# Explore_Labs_3D_Gyroscope_L3GD20H_Breako.net
KiCad netlist of a schematic drawn in EAGLE
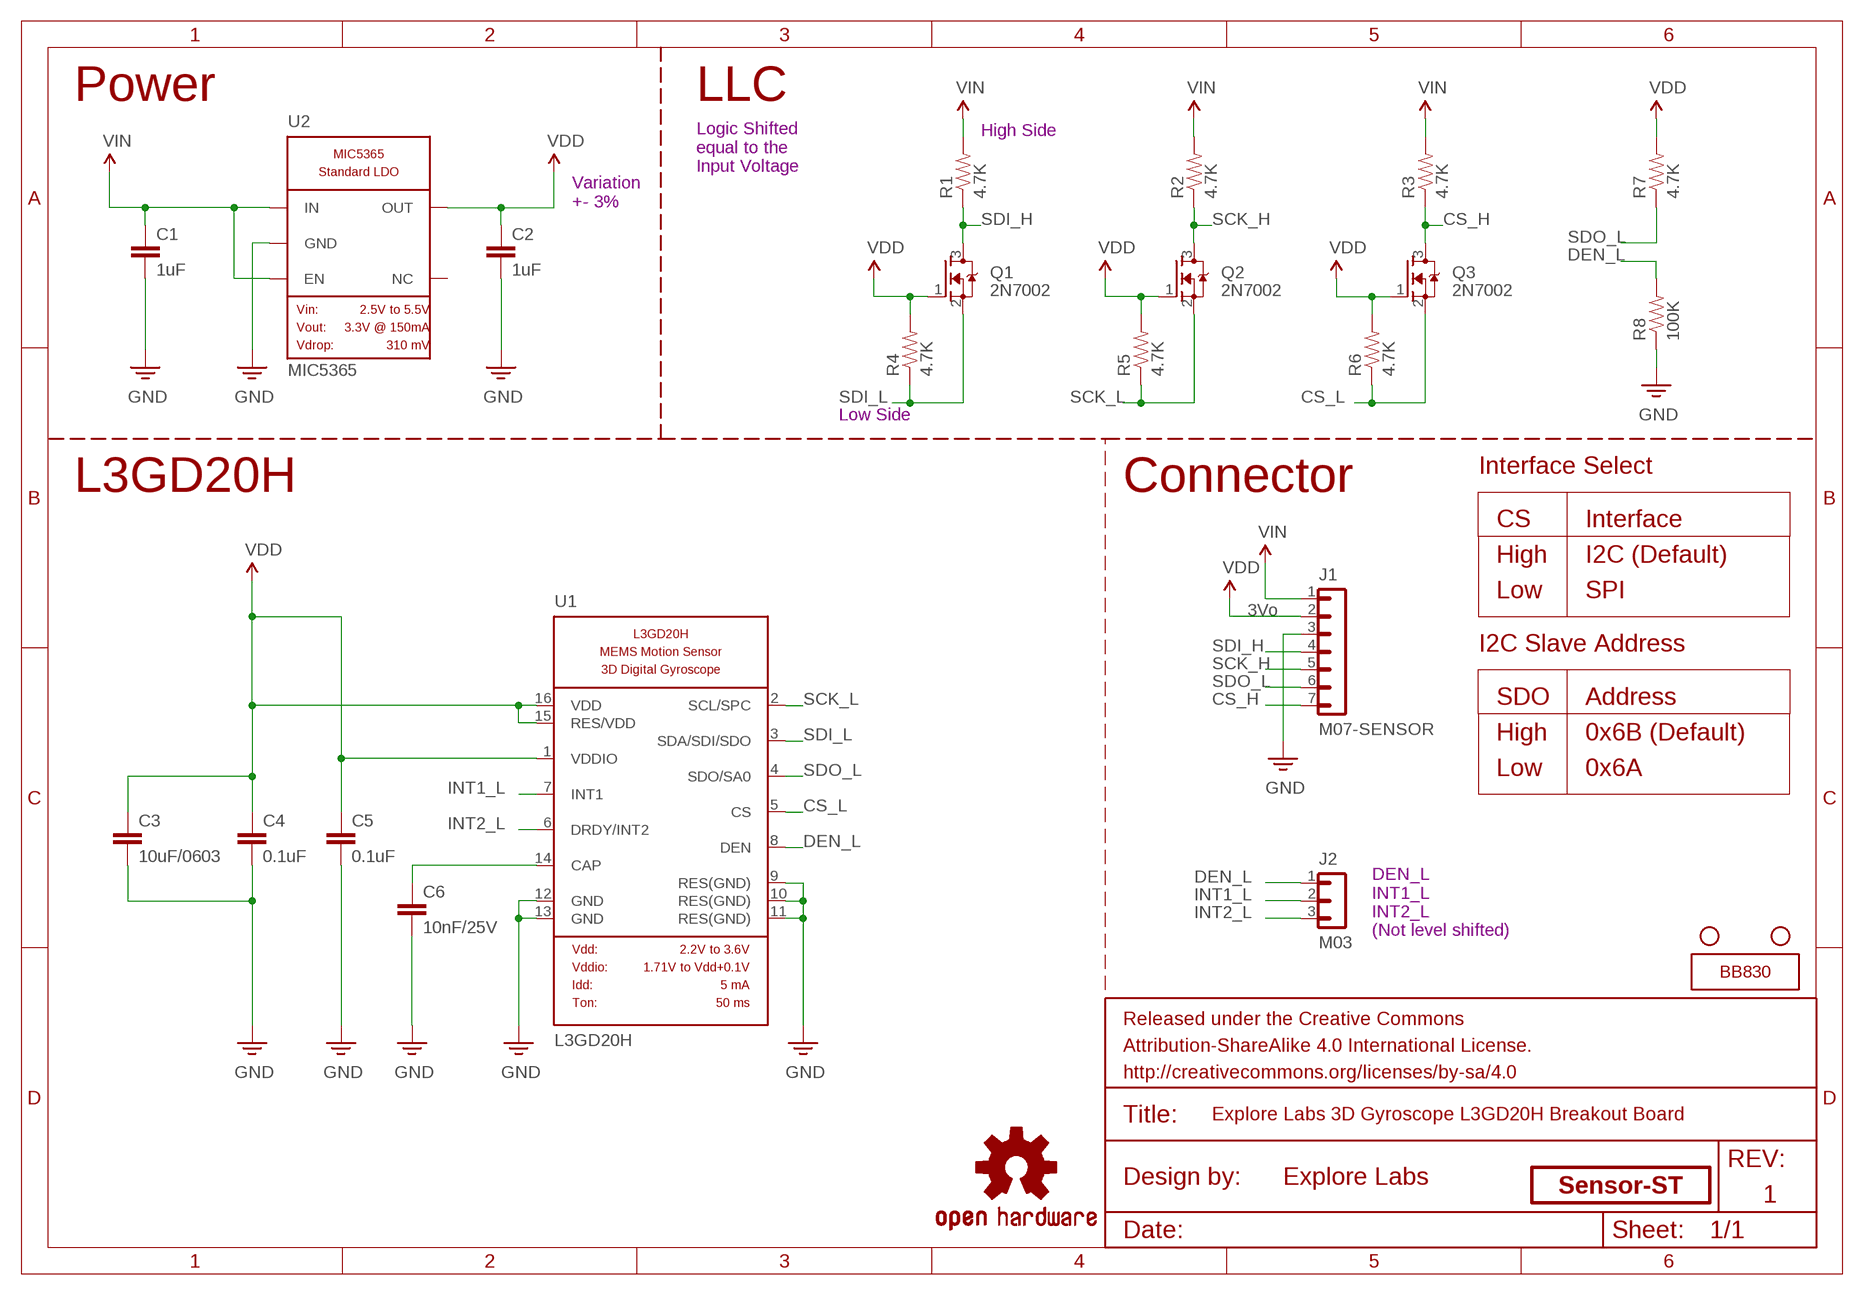
[diagram p0: schematic, sheet 1]

(export (version "E")
  (design (tool "Eeschema 10.0.6"))
  (components
    (comp (ref "C1")
      (value "1uF")
      (footprint "eagle-import:0402-CAP")
      (libsource (lib "eagle-import") (part "CAPACITOR-0402"))
    )
    (comp (ref "C2")
      (value "1uF")
      (footprint "eagle-import:0402-CAP")
      (libsource (lib "eagle-import") (part "CAPACITOR-0402"))
    )
    (comp (ref "C3")
      (value "10uF/0603")
      (footprint "eagle-import:0603-CAP")
      (libsource (lib "eagle-import") (part "CAPACITOR-0603"))
    )
    (comp (ref "C4")
      (value "0.1uF")
      (footprint "eagle-import:0402-CAP")
      (libsource (lib "eagle-import") (part "CAPACITOR-0402"))
    )
    (comp (ref "C5")
      (value "0.1uF")
      (footprint "eagle-import:0402-CAP")
      (libsource (lib "eagle-import") (part "CAPACITOR-0402"))
    )
    (comp (ref "C6")
      (value "10nF/25V")
      (footprint "eagle-import:0402-CAP")
      (libsource (lib "eagle-import") (part "CAPACITOR-0402"))
    )
    (comp (ref "H1")
      (value "STAND-OFF")
      (footprint "eagle-import:STAND-OFF")
      (libsource (lib "eagle-import") (part "STAND-OFF"))
    )
    (comp (ref "H2")
      (value "STAND-OFF")
      (footprint "eagle-import:STAND-OFF")
      (libsource (lib "eagle-import") (part "STAND-OFF"))
    )
    (comp (ref "J1")
      (value "M07-SENSOR")
      (footprint "eagle-import:1X07-SENSOR-SPI")
      (libsource (lib "eagle-import") (part "M07-SENSOR"))
    )
    (comp (ref "J2")
      (value "M03")
      (footprint "eagle-import:1X03")
      (libsource (lib "eagle-import") (part "M03"))
    )
    (comp (ref "Q1")
      (value "2N7002")
      (footprint "eagle-import:SOT23")
      (libsource (lib "eagle-import") (part "MOSFET-N-2N7002P"))
    )
    (comp (ref "Q2")
      (value "2N7002")
      (footprint "eagle-import:SOT23")
      (libsource (lib "eagle-import") (part "MOSFET-N-2N7002P"))
    )
    (comp (ref "Q3")
      (value "2N7002")
      (footprint "eagle-import:SOT23")
      (libsource (lib "eagle-import") (part "MOSFET-N-2N7002P"))
    )
    (comp (ref "R1")
      (value "4.7K")
      (footprint "eagle-import:0402-RES")
      (libsource (lib "eagle-import") (part "RESISTOR-0402"))
    )
    (comp (ref "R2")
      (value "4.7K")
      (footprint "eagle-import:0402-RES")
      (libsource (lib "eagle-import") (part "RESISTOR-0402"))
    )
    (comp (ref "R3")
      (value "4.7K")
      (footprint "eagle-import:0402-RES")
      (libsource (lib "eagle-import") (part "RESISTOR-0402"))
    )
    (comp (ref "R4")
      (value "4.7K")
      (footprint "eagle-import:0402-RES")
      (libsource (lib "eagle-import") (part "RESISTOR-0402"))
    )
    (comp (ref "R5")
      (value "4.7K")
      (footprint "eagle-import:0402-RES")
      (libsource (lib "eagle-import") (part "RESISTOR-0402"))
    )
    (comp (ref "R6")
      (value "4.7K")
      (footprint "eagle-import:0402-RES")
      (libsource (lib "eagle-import") (part "RESISTOR-0402"))
    )
    (comp (ref "R7")
      (value "4.7K")
      (footprint "eagle-import:0402-RES")
      (libsource (lib "eagle-import") (part "RESISTOR-0402"))
    )
    (comp (ref "R8")
      (value "100K")
      (footprint "eagle-import:0402-RES")
      (libsource (lib "eagle-import") (part "RESISTOR-0402"))
    )
    (comp (ref "U1")
      (value "L3GD20H")
      (footprint "eagle-import:LGA16")
      (libsource (lib "eagle-import") (part "L3GD20H"))
    )
    (comp (ref "U2")
      (value "MIC5365")
      (footprint "eagle-import:SOT23-LDO")
      (libsource (lib "eagle-import") (part "MIC5365"))
    )
    (comp (ref "ZZ1")
      (value "EXPLORE-LABS-LOGO-2-0.25")
      (footprint "eagle-import:EXLABS_LOGO_0.25")
      (libsource (lib "eagle-import") (part "EXPLORE-LABS-LOGO-2-0.25"))
    )
    (comp (ref "ZZ2")
      (value "OSHW-LOGOBOTTOM")
      (footprint "eagle-import:OSHW-LOGO-M-BOTTOM")
      (libsource (lib "eagle-import") (part "OSHW-LOGOBOTTOM"))
    )
    (comp (ref "ZZ3")
      (value "SENSOR-ST")
      (footprint "eagle-import:SENSOR-ST")
      (libsource (lib "eagle-import") (part "SENSOR-ST"))
    )
    (comp (ref "ZZ4")
      (value "BREADBOARD-830")
      (footprint "eagle-import:BREADBOARD-830")
      (libsource (lib "eagle-import") (part "BREADBOARD-830"))
    )
  )
  (nets
    (net (code "1") (name "/CS_H") (class "Default")
      (node (ref "J1") (pin "7") (pinfunction "7_7") (pintype "passive"))
      (node (ref "Q3") (pin "3") (pinfunction "D_3") (pintype "bidirectional"))
      (node (ref "R3") (pin "1") (pinfunction "1_1") (pintype "passive"))
    )
    (net (code "2") (name "/CS_L") (class "Default")
      (node (ref "Q3") (pin "2") (pinfunction "S_2") (pintype "bidirectional"))
      (node (ref "R6") (pin "1") (pinfunction "1_1") (pintype "passive"))
      (node (ref "U1") (pin "5") (pinfunction "CS_5") (pintype "bidirectional"))
    )
    (net (code "3") (name "/DEN_L") (class "Default")
      (node (ref "J2") (pin "1") (pinfunction "1_1") (pintype "passive"))
      (node (ref "R8") (pin "2") (pinfunction "2_2") (pintype "passive"))
      (node (ref "U1") (pin "8") (pinfunction "DEN_8") (pintype "bidirectional"))
    )
    (net (code "4") (name "/INT1_L") (class "Default")
      (node (ref "J2") (pin "2") (pinfunction "2_2") (pintype "passive"))
      (node (ref "U1") (pin "7") (pinfunction "INT1_7") (pintype "bidirectional"))
    )
    (net (code "5") (name "/INT2_L") (class "Default")
      (node (ref "J2") (pin "3") (pinfunction "3_3") (pintype "passive"))
      (node (ref "U1") (pin "6") (pinfunction "DRDY/INT2_6") (pintype "bidirectional"))
    )
    (net (code "6") (name "/SCK_H") (class "Default")
      (node (ref "J1") (pin "5") (pinfunction "5_5") (pintype "passive"))
      (node (ref "Q2") (pin "3") (pinfunction "D_3") (pintype "bidirectional"))
      (node (ref "R2") (pin "1") (pinfunction "1_1") (pintype "passive"))
    )
    (net (code "7") (name "/SCK_L") (class "Default")
      (node (ref "Q2") (pin "2") (pinfunction "S_2") (pintype "bidirectional"))
      (node (ref "R5") (pin "1") (pinfunction "1_1") (pintype "passive"))
      (node (ref "U1") (pin "2") (pinfunction "SCL/SPC_2") (pintype "bidirectional"))
    )
    (net (code "8") (name "/SDI_H") (class "Default")
      (node (ref "J1") (pin "4") (pinfunction "4_4") (pintype "passive"))
      (node (ref "Q1") (pin "3") (pinfunction "D_3") (pintype "bidirectional"))
      (node (ref "R1") (pin "1") (pinfunction "1_1") (pintype "passive"))
    )
    (net (code "9") (name "/SDI_L") (class "Default")
      (node (ref "Q1") (pin "2") (pinfunction "S_2") (pintype "bidirectional"))
      (node (ref "R4") (pin "1") (pinfunction "1_1") (pintype "passive"))
      (node (ref "U1") (pin "3") (pinfunction "SDA/SDI/SDO_3") (pintype "bidirectional"))
    )
    (net (code "10") (name "/SDO_L") (class "Default")
      (node (ref "J1") (pin "6") (pinfunction "6_6") (pintype "passive"))
      (node (ref "R7") (pin "1") (pinfunction "1_1") (pintype "passive"))
      (node (ref "U1") (pin "4") (pinfunction "SDO/SA0_4") (pintype "bidirectional"))
    )
    (net (code "11") (name "GND") (class "Default")
      (node (ref "C1") (pin "2") (pinfunction "2_2") (pintype "passive"))
      (node (ref "C2") (pin "2") (pinfunction "2_2") (pintype "passive"))
      (node (ref "C3") (pin "2") (pinfunction "2_2") (pintype "passive"))
      (node (ref "C4") (pin "2") (pinfunction "2_2") (pintype "passive"))
      (node (ref "C5") (pin "2") (pinfunction "2_2") (pintype "passive"))
      (node (ref "C6") (pin "2") (pinfunction "2_2") (pintype "passive"))
      (node (ref "J1") (pin "3") (pinfunction "3_3") (pintype "passive"))
      (node (ref "R8") (pin "1") (pinfunction "1_1") (pintype "passive"))
      (node (ref "U1") (pin "10") (pinfunction "RES(GND)_10") (pintype "power_in"))
      (node (ref "U1") (pin "11") (pinfunction "RES(GND)_11") (pintype "power_in"))
      (node (ref "U1") (pin "12") (pinfunction "GND_12") (pintype "power_in"))
      (node (ref "U1") (pin "13") (pinfunction "GND_13") (pintype "power_in"))
      (node (ref "U1") (pin "9") (pinfunction "RES(GND)_9") (pintype "power_in"))
      (node (ref "U2") (pin "2") (pinfunction "GND_2") (pintype "power_in"))
    )
    (net (code "12") (name "Net-(U1-CAP)") (class "Default")
      (node (ref "C6") (pin "1") (pinfunction "1_1") (pintype "passive"))
      (node (ref "U1") (pin "14") (pinfunction "CAP_14") (pintype "bidirectional"))
    )
    (net (code "13") (name "VDD") (class "Default")
      (node (ref "C2") (pin "1") (pinfunction "1_1") (pintype "passive"))
      (node (ref "C3") (pin "1") (pinfunction "1_1") (pintype "passive"))
      (node (ref "C4") (pin "1") (pinfunction "1_1") (pintype "passive"))
      (node (ref "C5") (pin "1") (pinfunction "1_1") (pintype "passive"))
      (node (ref "J1") (pin "2") (pinfunction "2_2") (pintype "passive"))
      (node (ref "Q1") (pin "1") (pinfunction "G_1") (pintype "bidirectional"))
      (node (ref "Q2") (pin "1") (pinfunction "G_1") (pintype "bidirectional"))
      (node (ref "Q3") (pin "1") (pinfunction "G_1") (pintype "bidirectional"))
      (node (ref "R4") (pin "2") (pinfunction "2_2") (pintype "passive"))
      (node (ref "R5") (pin "2") (pinfunction "2_2") (pintype "passive"))
      (node (ref "R6") (pin "2") (pinfunction "2_2") (pintype "passive"))
      (node (ref "R7") (pin "2") (pinfunction "2_2") (pintype "passive"))
      (node (ref "U1") (pin "1") (pinfunction "VDDIO_1") (pintype "power_in"))
      (node (ref "U1") (pin "15") (pinfunction "RES/VDD_15") (pintype "power_in"))
      (node (ref "U1") (pin "16") (pinfunction "VDD_16") (pintype "power_in"))
      (node (ref "U2") (pin "5") (pinfunction "OUT_5") (pintype "power_in"))
    )
    (net (code "14") (name "VIN") (class "Default")
      (node (ref "C1") (pin "1") (pinfunction "1_1") (pintype "passive"))
      (node (ref "J1") (pin "1") (pinfunction "1_1") (pintype "passive"))
      (node (ref "R1") (pin "2") (pinfunction "2_2") (pintype "passive"))
      (node (ref "R2") (pin "2") (pinfunction "2_2") (pintype "passive"))
      (node (ref "R3") (pin "2") (pinfunction "2_2") (pintype "passive"))
      (node (ref "U2") (pin "1") (pinfunction "IN_1") (pintype "power_in"))
      (node (ref "U2") (pin "3") (pinfunction "EN_3") (pintype "input"))
    )
    (net (code "15") (name "unconnected-(U2-NC-Pad4)") (class "Default")
      (node (ref "U2") (pin "4") (pinfunction "NC_4") (pintype "no_connect"))
    )
  )
)
